# Sheet4.net
KiCad netlist of a schematic drawn in Altium Designer
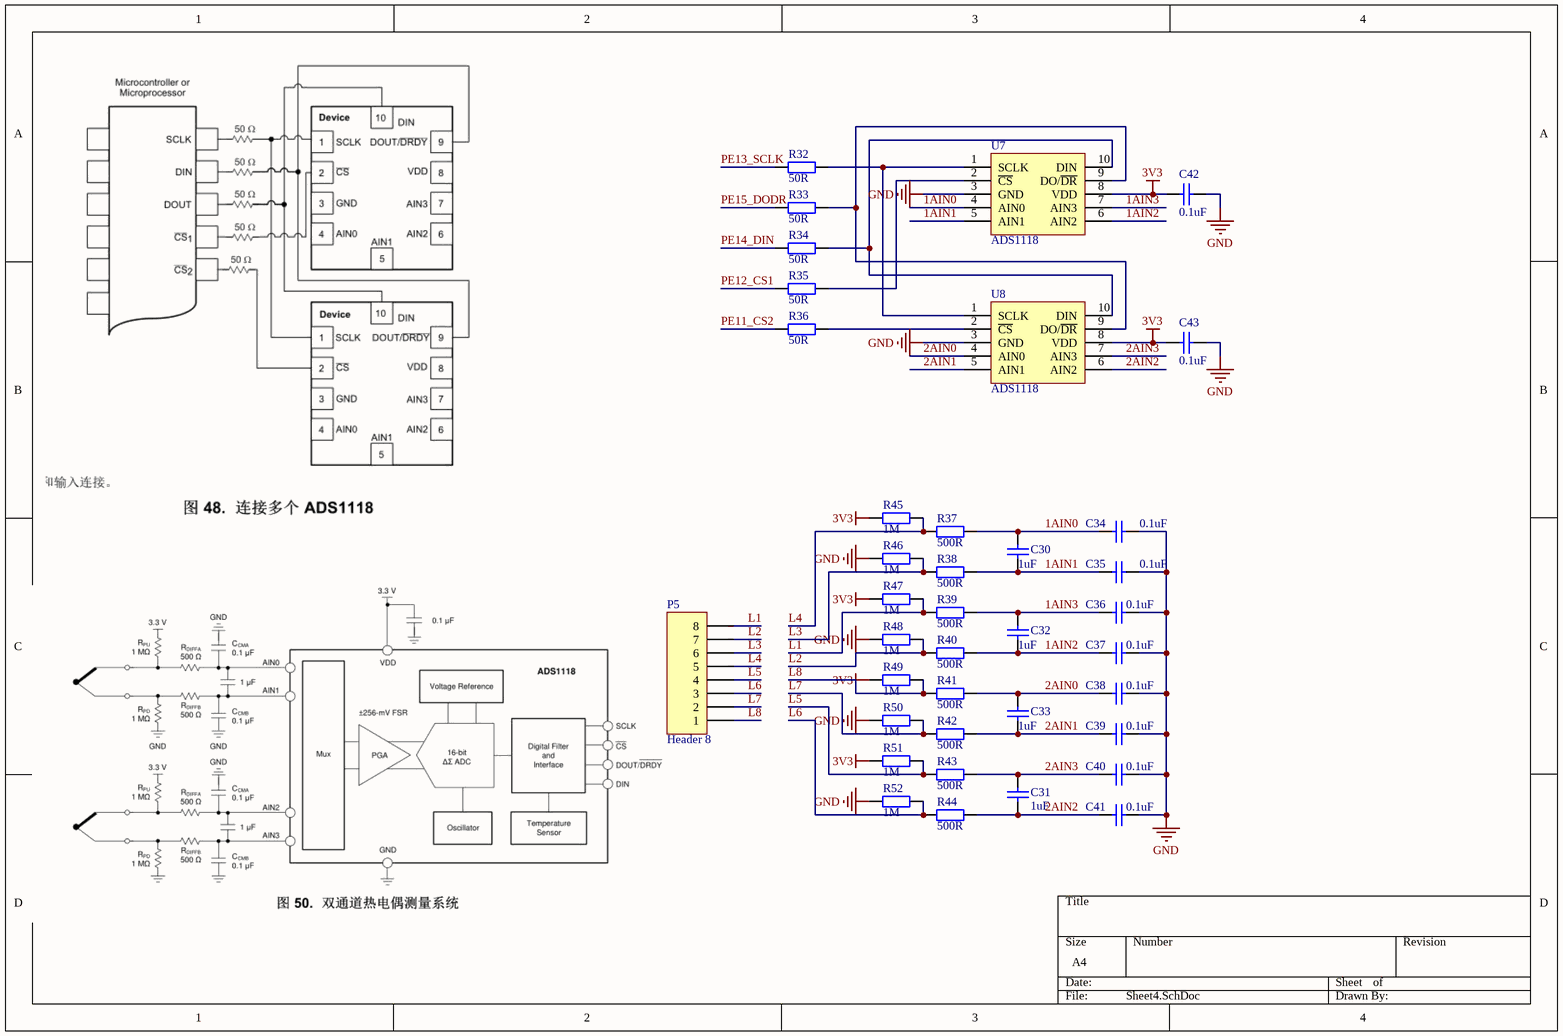
[diagram p0: Sheet4.SchDoc]

(export (version "E")
  (design (tool "Eeschema 10.0.6"))
  (components
    (comp (ref "C30")
      (value "1uF")
      (footprint "LC-0603_C")
      (description "贴片电容")
      (libsource (lib "Miscellaneous Devices LC") (part "0603 1uF (105) 10% 50V"))
    )
    (comp (ref "C31")
      (value "1uF")
      (footprint "LC-0603_C")
      (description "贴片电容")
      (libsource (lib "Miscellaneous Devices LC") (part "0603 1uF (105) 10% 50V"))
    )
    (comp (ref "C32")
      (value "1uF")
      (footprint "LC-0603_C")
      (description "贴片电容")
      (libsource (lib "Miscellaneous Devices LC") (part "0603 1uF (105) 10% 50V"))
    )
    (comp (ref "C33")
      (value "1uF")
      (footprint "LC-0603_C")
      (description "贴片电容")
      (libsource (lib "Miscellaneous Devices LC") (part "0603 1uF (105) 10% 50V"))
    )
    (comp (ref "C34")
      (value "0.1uF")
      (footprint "LC-0603_C")
      (description "贴片电容")
      (libsource (lib "Miscellaneous Devices LC") (part "0603 1uF (105) 10% 50V"))
    )
    (comp (ref "C35")
      (value "0.1uF")
      (footprint "LC-0603_C")
      (description "贴片电容")
      (libsource (lib "Miscellaneous Devices LC") (part "0603 1uF (105) 10% 50V"))
    )
    (comp (ref "C36")
      (value "0.1uF")
      (footprint "LC-0603_C")
      (description "贴片电容")
      (libsource (lib "Miscellaneous Devices LC") (part "0603 1uF (105) 10% 50V"))
    )
    (comp (ref "C37")
      (value "0.1uF")
      (footprint "LC-0603_C")
      (description "贴片电容")
      (libsource (lib "Miscellaneous Devices LC") (part "0603 1uF (105) 10% 50V"))
    )
    (comp (ref "C38")
      (value "0.1uF")
      (footprint "LC-0603_C")
      (description "贴片电容")
      (libsource (lib "Miscellaneous Devices LC") (part "0603 1uF (105) 10% 50V"))
    )
    (comp (ref "C39")
      (value "0.1uF")
      (footprint "LC-0603_C")
      (description "贴片电容")
      (libsource (lib "Miscellaneous Devices LC") (part "0603 1uF (105) 10% 50V"))
    )
    (comp (ref "C40")
      (value "0.1uF")
      (footprint "LC-0603_C")
      (description "贴片电容")
      (libsource (lib "Miscellaneous Devices LC") (part "0603 1uF (105) 10% 50V"))
    )
    (comp (ref "C41")
      (value "0.1uF")
      (footprint "LC-0603_C")
      (description "贴片电容")
      (libsource (lib "Miscellaneous Devices LC") (part "0603 1uF (105) 10% 50V"))
    )
    (comp (ref "C42")
      (value "0.1uF")
      (footprint "LC-0603_C")
      (description "贴片电容")
      (libsource (lib "Miscellaneous Devices LC") (part "0603 1uF (105) 10% 50V"))
    )
    (comp (ref "C43")
      (value "0.1uF")
      (footprint "LC-0603_C")
      (description "贴片电容")
      (libsource (lib "Miscellaneous Devices LC") (part "0603 1uF (105) 10% 50V"))
    )
    (comp (ref "P5")
      (value "Header 8")
      (footprint "HDR1X8")
      (description "Header, 8-Pin")
      (fields (field (name "PUBLISHER") "Altium Limited"))
      (libsource (lib "Sparks") (part "Header 8"))
    )
    (comp (ref "R32")
      (value "50R")
      (footprint "LC-0603_R")
      (description "贴片电阻")
      (libsource (lib "Miscellaneous Devices LC") (part "0603 1.5KΩ (1501) 1%"))
    )
    (comp (ref "R33")
      (value "50R")
      (footprint "LC-0603_R")
      (description "贴片电阻")
      (libsource (lib "Miscellaneous Devices LC") (part "0603 1.5KΩ (1501) 1%"))
    )
    (comp (ref "R34")
      (value "50R")
      (footprint "LC-0603_R")
      (description "贴片电阻")
      (libsource (lib "Miscellaneous Devices LC") (part "0603 1.5KΩ (1501) 1%"))
    )
    (comp (ref "R35")
      (value "50R")
      (footprint "LC-0603_R")
      (description "贴片电阻")
      (libsource (lib "Miscellaneous Devices LC") (part "0603 1.5KΩ (1501) 1%"))
    )
    (comp (ref "R36")
      (value "50R")
      (footprint "LC-0603_R")
      (description "贴片电阻")
      (libsource (lib "Miscellaneous Devices LC") (part "0603 1.5KΩ (1501) 1%"))
    )
    (comp (ref "R37")
      (value "500R")
      (footprint "LC-0603_R")
      (description "贴片电阻")
      (libsource (lib "Miscellaneous Devices LC") (part "0603 1.5KΩ (1501) 1%"))
    )
    (comp (ref "R38")
      (value "500R")
      (footprint "LC-0603_R")
      (description "贴片电阻")
      (libsource (lib "Miscellaneous Devices LC") (part "0603 1.5KΩ (1501) 1%"))
    )
    (comp (ref "R39")
      (value "500R")
      (footprint "LC-0603_R")
      (description "贴片电阻")
      (libsource (lib "Miscellaneous Devices LC") (part "0603 1.5KΩ (1501) 1%"))
    )
    (comp (ref "R40")
      (value "500R")
      (footprint "LC-0603_R")
      (description "贴片电阻")
      (libsource (lib "Miscellaneous Devices LC") (part "0603 1.5KΩ (1501) 1%"))
    )
    (comp (ref "R41")
      (value "500R")
      (footprint "LC-0603_R")
      (description "贴片电阻")
      (libsource (lib "Miscellaneous Devices LC") (part "0603 1.5KΩ (1501) 1%"))
    )
    (comp (ref "R42")
      (value "500R")
      (footprint "LC-0603_R")
      (description "贴片电阻")
      (libsource (lib "Miscellaneous Devices LC") (part "0603 1.5KΩ (1501) 1%"))
    )
    (comp (ref "R43")
      (value "500R")
      (footprint "LC-0603_R")
      (description "贴片电阻")
      (libsource (lib "Miscellaneous Devices LC") (part "0603 1.5KΩ (1501) 1%"))
    )
    (comp (ref "R44")
      (value "500R")
      (footprint "LC-0603_R")
      (description "贴片电阻")
      (libsource (lib "Miscellaneous Devices LC") (part "0603 1.5KΩ (1501) 1%"))
    )
    (comp (ref "R45")
      (value "1M")
      (footprint "LC-0603_R")
      (description "贴片电阻")
      (libsource (lib "Miscellaneous Devices LC") (part "0603 1.5KΩ (1501) 1%"))
    )
    (comp (ref "R46")
      (value "1M")
      (footprint "LC-0603_R")
      (description "贴片电阻")
      (libsource (lib "Miscellaneous Devices LC") (part "0603 1.5KΩ (1501) 1%"))
    )
    (comp (ref "R47")
      (value "1M")
      (footprint "LC-0603_R")
      (description "贴片电阻")
      (libsource (lib "Miscellaneous Devices LC") (part "0603 1.5KΩ (1501) 1%"))
    )
    (comp (ref "R48")
      (value "1M")
      (footprint "LC-0603_R")
      (description "贴片电阻")
      (libsource (lib "Miscellaneous Devices LC") (part "0603 1.5KΩ (1501) 1%"))
    )
    (comp (ref "R49")
      (value "1M")
      (footprint "LC-0603_R")
      (description "贴片电阻")
      (libsource (lib "Miscellaneous Devices LC") (part "0603 1.5KΩ (1501) 1%"))
    )
    (comp (ref "R50")
      (value "1M")
      (footprint "LC-0603_R")
      (description "贴片电阻")
      (libsource (lib "Miscellaneous Devices LC") (part "0603 1.5KΩ (1501) 1%"))
    )
    (comp (ref "R51")
      (value "1M")
      (footprint "LC-0603_R")
      (description "贴片电阻")
      (libsource (lib "Miscellaneous Devices LC") (part "0603 1.5KΩ (1501) 1%"))
    )
    (comp (ref "R52")
      (value "1M")
      (footprint "LC-0603_R")
      (description "贴片电阻")
      (libsource (lib "Miscellaneous Devices LC") (part "0603 1.5KΩ (1501) 1%"))
    )
    (comp (ref "U7")
      (value "ADS1118")
      (footprint "SOP-10")
      (description "AD采集芯片")
      (libsource (lib "liu_2016") (part "ADS1118"))
    )
    (comp (ref "U8")
      (value "ADS1118")
      (footprint "SOP-10")
      (description "AD采集芯片")
      (libsource (lib "liu_2016") (part "ADS1118"))
    )
  )
  (nets
    (net (code "1") (name "/1AIN0") (class "Default")
      (node (ref "C30") (pin "2") (pinfunction "2_2") (pintype "passive"))
      (node (ref "C34") (pin "1") (pinfunction "1_1") (pintype "passive"))
      (node (ref "R37") (pin "2") (pinfunction "2_2") (pintype "passive"))
      (node (ref "U7") (pin "4") (pinfunction "AIN0_4") (pintype "passive"))
    )
    (net (code "2") (name "/1AIN1") (class "Default")
      (node (ref "C30") (pin "1") (pinfunction "1_1") (pintype "passive"))
      (node (ref "C35") (pin "1") (pinfunction "1_1") (pintype "passive"))
      (node (ref "R38") (pin "2") (pinfunction "2_2") (pintype "passive"))
      (node (ref "U7") (pin "5") (pinfunction "AIN1_5") (pintype "passive"))
    )
    (net (code "3") (name "/1AIN2") (class "Default")
      (node (ref "C32") (pin "1") (pinfunction "1_1") (pintype "passive"))
      (node (ref "C37") (pin "1") (pinfunction "1_1") (pintype "passive"))
      (node (ref "R40") (pin "2") (pinfunction "2_2") (pintype "passive"))
      (node (ref "U7") (pin "6") (pinfunction "AIN2_6") (pintype "passive"))
    )
    (net (code "4") (name "/1AIN3") (class "Default")
      (node (ref "C32") (pin "2") (pinfunction "2_2") (pintype "passive"))
      (node (ref "C36") (pin "1") (pinfunction "1_1") (pintype "passive"))
      (node (ref "R39") (pin "2") (pinfunction "2_2") (pintype "passive"))
      (node (ref "U7") (pin "7") (pinfunction "AIN3_7") (pintype "passive"))
    )
    (net (code "5") (name "/2AIN0") (class "Default")
      (node (ref "C33") (pin "2") (pinfunction "2_2") (pintype "passive"))
      (node (ref "C38") (pin "1") (pinfunction "1_1") (pintype "passive"))
      (node (ref "R41") (pin "2") (pinfunction "2_2") (pintype "passive"))
      (node (ref "U8") (pin "4") (pinfunction "AIN0_4") (pintype "passive"))
    )
    (net (code "6") (name "/2AIN1") (class "Default")
      (node (ref "C33") (pin "1") (pinfunction "1_1") (pintype "passive"))
      (node (ref "C39") (pin "1") (pinfunction "1_1") (pintype "passive"))
      (node (ref "R42") (pin "2") (pinfunction "2_2") (pintype "passive"))
      (node (ref "U8") (pin "5") (pinfunction "AIN1_5") (pintype "passive"))
    )
    (net (code "7") (name "/2AIN2") (class "Default")
      (node (ref "C31") (pin "1") (pinfunction "1_1") (pintype "passive"))
      (node (ref "C41") (pin "1") (pinfunction "1_1") (pintype "passive"))
      (node (ref "R44") (pin "2") (pinfunction "2_2") (pintype "passive"))
      (node (ref "U8") (pin "6") (pinfunction "AIN2_6") (pintype "passive"))
    )
    (net (code "8") (name "/2AIN3") (class "Default")
      (node (ref "C31") (pin "2") (pinfunction "2_2") (pintype "passive"))
      (node (ref "C40") (pin "1") (pinfunction "1_1") (pintype "passive"))
      (node (ref "R43") (pin "2") (pinfunction "2_2") (pintype "passive"))
      (node (ref "U8") (pin "7") (pinfunction "AIN3_7") (pintype "passive"))
    )
    (net (code "9") (name "/L1") (class "Default")
      (node (ref "P5") (pin "8") (pinfunction "8_8") (pintype "passive"))
      (node (ref "R39") (pin "1") (pinfunction "1_1") (pintype "passive"))
      (node (ref "R47") (pin "2") (pinfunction "2_2") (pintype "passive"))
    )
    (net (code "10") (name "/L2") (class "Default")
      (node (ref "P5") (pin "7") (pinfunction "7_7") (pintype "passive"))
      (node (ref "R40") (pin "1") (pinfunction "1_1") (pintype "passive"))
      (node (ref "R48") (pin "2") (pinfunction "2_2") (pintype "passive"))
    )
    (net (code "11") (name "/L3") (class "Default")
      (node (ref "P5") (pin "6") (pinfunction "6_6") (pintype "passive"))
      (node (ref "R38") (pin "1") (pinfunction "1_1") (pintype "passive"))
      (node (ref "R46") (pin "2") (pinfunction "2_2") (pintype "passive"))
    )
    (net (code "12") (name "/L4") (class "Default")
      (node (ref "P5") (pin "5") (pinfunction "5_5") (pintype "passive"))
      (node (ref "R37") (pin "1") (pinfunction "1_1") (pintype "passive"))
      (node (ref "R45") (pin "2") (pinfunction "2_2") (pintype "passive"))
    )
    (net (code "13") (name "/L5") (class "Default")
      (node (ref "P5") (pin "4") (pinfunction "4_4") (pintype "passive"))
      (node (ref "R43") (pin "1") (pinfunction "1_1") (pintype "passive"))
      (node (ref "R51") (pin "2") (pinfunction "2_2") (pintype "passive"))
    )
    (net (code "14") (name "/L6") (class "Default")
      (node (ref "P5") (pin "3") (pinfunction "3_3") (pintype "passive"))
      (node (ref "R44") (pin "1") (pinfunction "1_1") (pintype "passive"))
      (node (ref "R52") (pin "2") (pinfunction "2_2") (pintype "passive"))
    )
    (net (code "15") (name "/L7") (class "Default")
      (node (ref "P5") (pin "2") (pinfunction "2_2") (pintype "passive"))
      (node (ref "R42") (pin "1") (pinfunction "1_1") (pintype "passive"))
      (node (ref "R50") (pin "2") (pinfunction "2_2") (pintype "passive"))
    )
    (net (code "16") (name "/L8") (class "Default")
      (node (ref "P5") (pin "1") (pinfunction "1_1") (pintype "passive"))
      (node (ref "R41") (pin "1") (pinfunction "1_1") (pintype "passive"))
      (node (ref "R49") (pin "2") (pinfunction "2_2") (pintype "passive"))
    )
    (net (code "17") (name "/PE11_CS2") (class "Default")
      (node (ref "R36") (pin "1") (pinfunction "1_1") (pintype "passive"))
    )
    (net (code "18") (name "/PE12_CS1") (class "Default")
      (node (ref "R35") (pin "1") (pinfunction "1_1") (pintype "passive"))
    )
    (net (code "19") (name "/PE13_SCLK") (class "Default")
      (node (ref "R32") (pin "1") (pinfunction "1_1") (pintype "passive"))
    )
    (net (code "20") (name "/PE14_DIN") (class "Default")
      (node (ref "R34") (pin "1") (pinfunction "1_1") (pintype "passive"))
    )
    (net (code "21") (name "/PE15_DODR") (class "Default")
      (node (ref "R33") (pin "1") (pinfunction "1_1") (pintype "passive"))
    )
    (net (code "22") (name "3V3") (class "Default")
      (node (ref "C42") (pin "1") (pinfunction "1_1") (pintype "passive"))
      (node (ref "C43") (pin "1") (pinfunction "1_1") (pintype "passive"))
      (node (ref "R45") (pin "1") (pinfunction "1_1") (pintype "passive"))
      (node (ref "R47") (pin "1") (pinfunction "1_1") (pintype "passive"))
      (node (ref "R49") (pin "1") (pinfunction "1_1") (pintype "passive"))
      (node (ref "R51") (pin "1") (pinfunction "1_1") (pintype "passive"))
      (node (ref "U7") (pin "8") (pinfunction "VDD_8") (pintype "passive"))
      (node (ref "U8") (pin "8") (pinfunction "VDD_8") (pintype "passive"))
    )
    (net (code "23") (name "GND") (class "Default")
      (node (ref "C34") (pin "2") (pinfunction "2_2") (pintype "passive"))
      (node (ref "C35") (pin "2") (pinfunction "2_2") (pintype "passive"))
      (node (ref "C36") (pin "2") (pinfunction "2_2") (pintype "passive"))
      (node (ref "C37") (pin "2") (pinfunction "2_2") (pintype "passive"))
      (node (ref "C38") (pin "2") (pinfunction "2_2") (pintype "passive"))
      (node (ref "C39") (pin "2") (pinfunction "2_2") (pintype "passive"))
      (node (ref "C40") (pin "2") (pinfunction "2_2") (pintype "passive"))
      (node (ref "C41") (pin "2") (pinfunction "2_2") (pintype "passive"))
      (node (ref "C42") (pin "2") (pinfunction "2_2") (pintype "passive"))
      (node (ref "C43") (pin "2") (pinfunction "2_2") (pintype "passive"))
      (node (ref "R46") (pin "1") (pinfunction "1_1") (pintype "passive"))
      (node (ref "R48") (pin "1") (pinfunction "1_1") (pintype "passive"))
      (node (ref "R50") (pin "1") (pinfunction "1_1") (pintype "passive"))
      (node (ref "R52") (pin "1") (pinfunction "1_1") (pintype "passive"))
      (node (ref "U7") (pin "3") (pinfunction "GND_3") (pintype "passive"))
      (node (ref "U8") (pin "3") (pinfunction "GND_3") (pintype "passive"))
    )
    (net (code "24") (name "Net-(U7-DIN)") (class "Default")
      (node (ref "R34") (pin "2") (pinfunction "2_2") (pintype "passive"))
      (node (ref "U7") (pin "10") (pinfunction "DIN_10") (pintype "passive"))
      (node (ref "U8") (pin "10") (pinfunction "DIN_10") (pintype "passive"))
    )
    (net (code "25") (name "Net-(U7-DO{slash}~{DR})") (class "Default")
      (node (ref "R33") (pin "2") (pinfunction "2_2") (pintype "passive"))
      (node (ref "U7") (pin "9") (pinfunction "DO/~{DR}_9") (pintype "passive"))
      (node (ref "U8") (pin "9") (pinfunction "DO/~{DR}_9") (pintype "passive"))
    )
    (net (code "26") (name "Net-(U7-SCLK)") (class "Default")
      (node (ref "R32") (pin "2") (pinfunction "2_2") (pintype "passive"))
      (node (ref "U7") (pin "1") (pinfunction "SCLK_1") (pintype "passive"))
      (node (ref "U8") (pin "1") (pinfunction "SCLK_1") (pintype "passive"))
    )
    (net (code "27") (name "Net-(U7-~{CS})") (class "Default")
      (node (ref "R35") (pin "2") (pinfunction "2_2") (pintype "passive"))
      (node (ref "U7") (pin "2") (pinfunction "~{CS}_2") (pintype "passive"))
    )
    (net (code "28") (name "Net-(U8-~{CS})") (class "Default")
      (node (ref "R36") (pin "2") (pinfunction "2_2") (pintype "passive"))
      (node (ref "U8") (pin "2") (pinfunction "~{CS}_2") (pintype "passive"))
    )
  )
)
